# brose_24v_logic.net
KiCad netlist of a schematic drawn in EAGLE
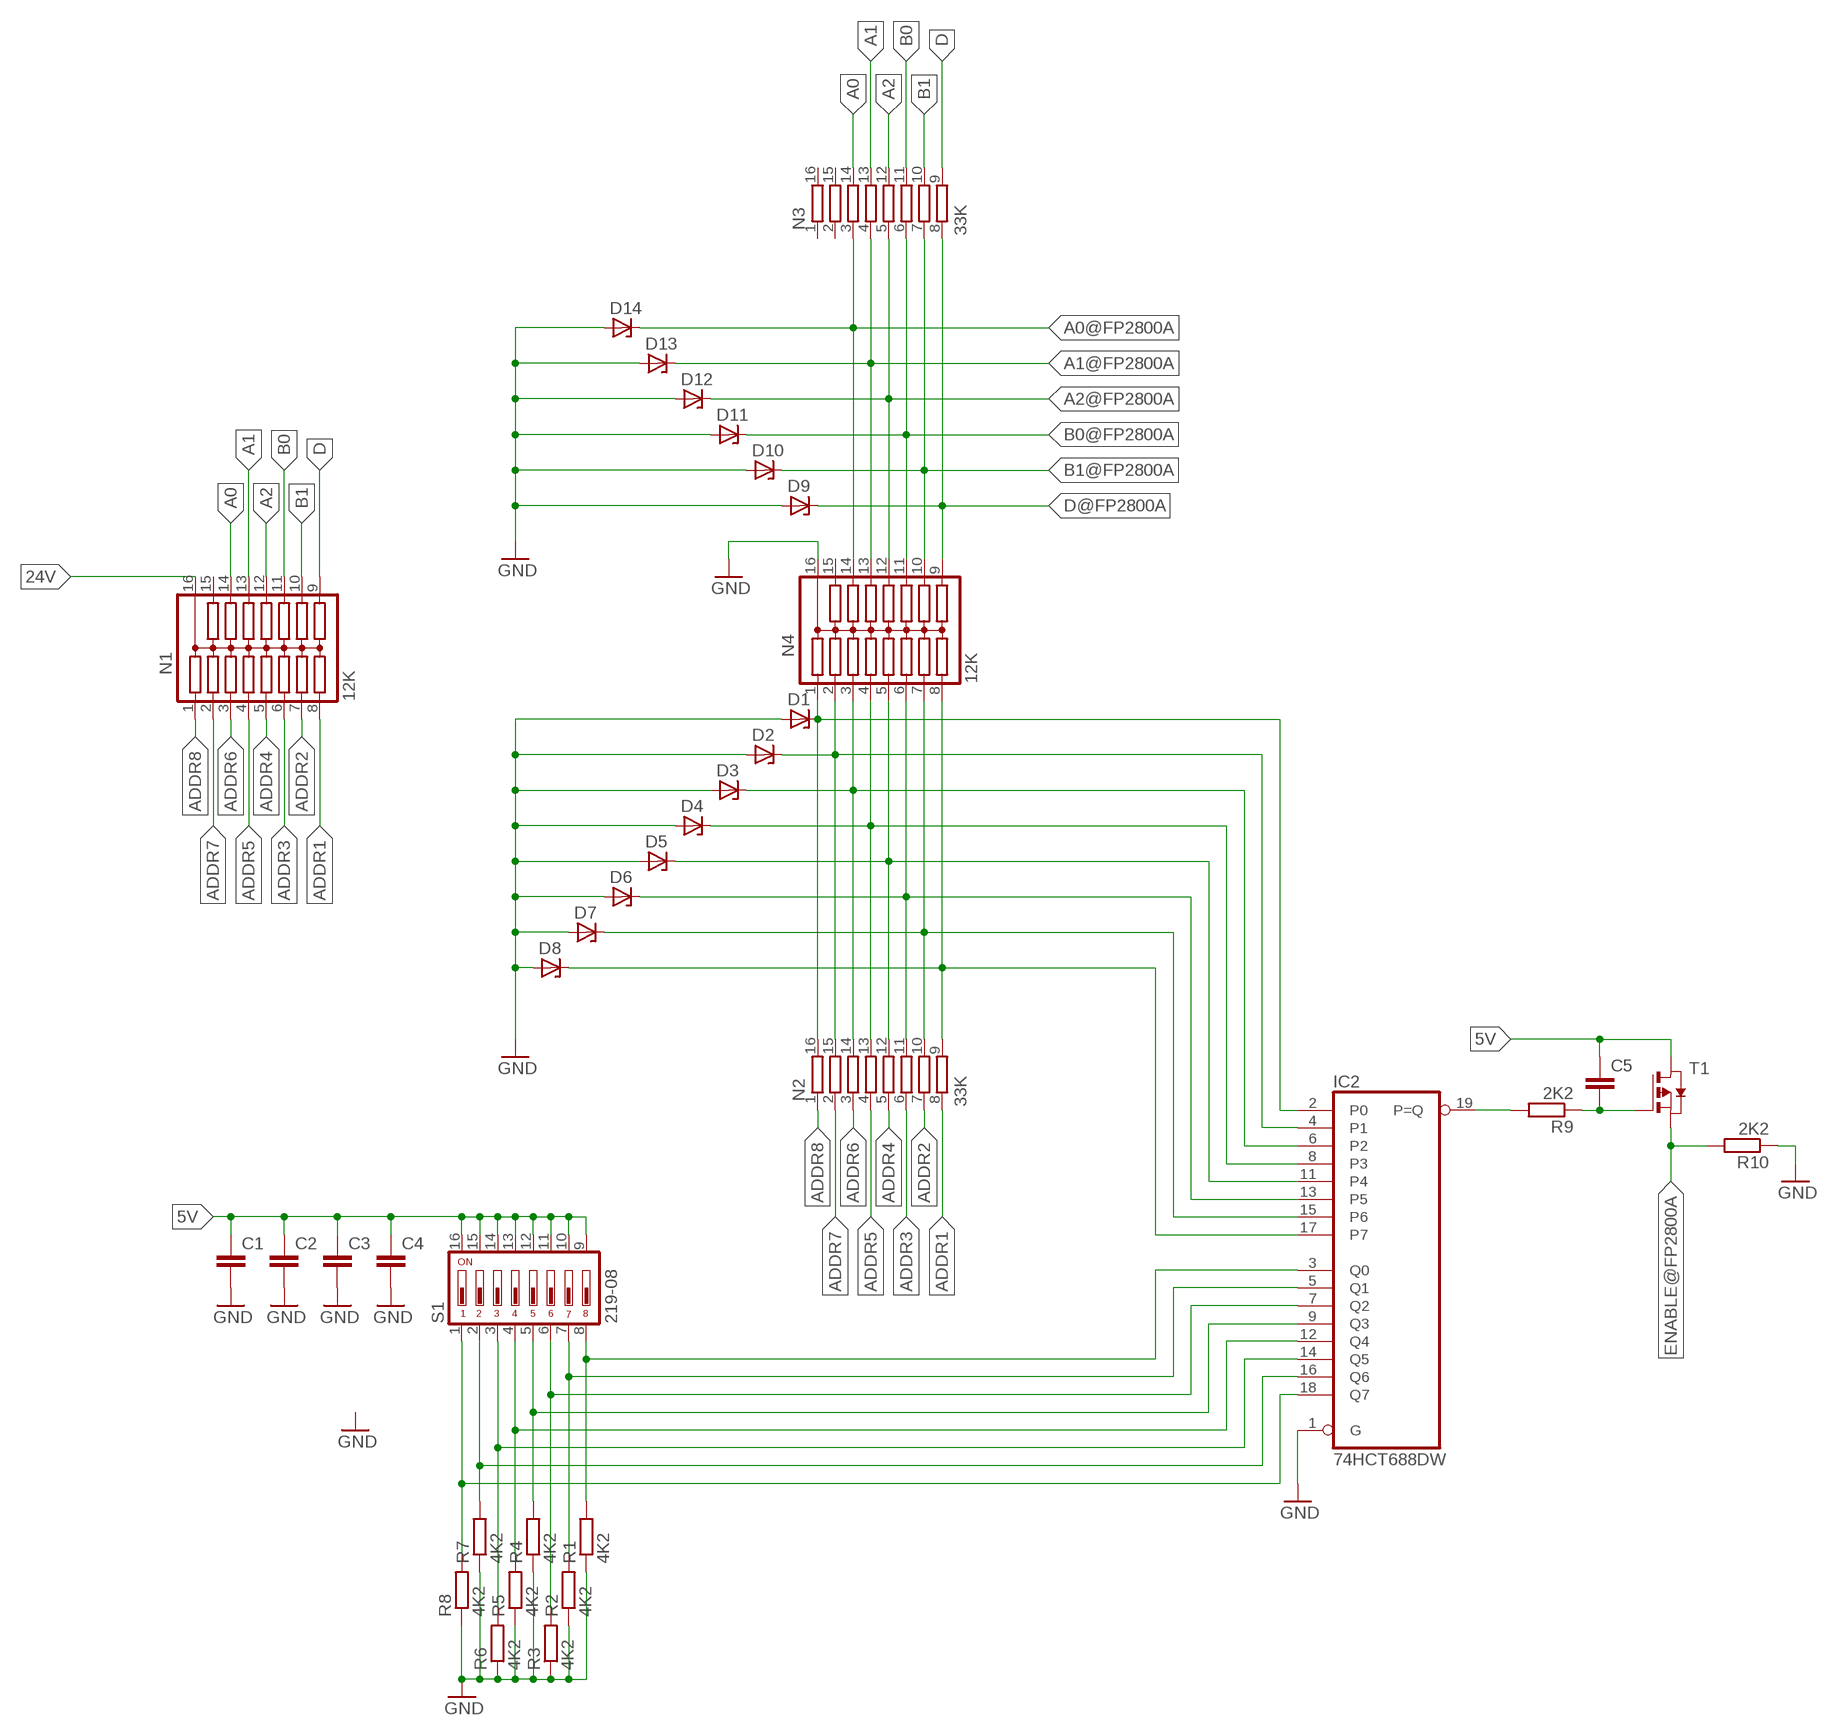
[diagram p0: schematic, sheet 1]

(export (version "E")
  (design (tool "Eeschema 10.0.6"))
  (components
    (comp (ref "C1")
      (value "C-EUC1206")
      (footprint "eagle-import:C1206")
      (libsource (lib "eagle-import") (part "C-EUC1206"))
    )
    (comp (ref "C2")
      (value "C-EUC1206")
      (footprint "eagle-import:C1206")
      (libsource (lib "eagle-import") (part "C-EUC1206"))
    )
    (comp (ref "C3")
      (value "C-EUC1206")
      (footprint "eagle-import:C1206")
      (libsource (lib "eagle-import") (part "C-EUC1206"))
    )
    (comp (ref "C4")
      (value "C-EUC1206")
      (footprint "eagle-import:C1206")
      (libsource (lib "eagle-import") (part "C-EUC1206"))
    )
    (comp (ref "C5")
      (value "C-EUC1206")
      (footprint "eagle-import:C1206")
      (libsource (lib "eagle-import") (part "C-EUC1206"))
    )
    (comp (ref "D1")
      (value "ZENER-DIODESMB")
      (footprint "eagle-import:SMB")
      (libsource (lib "eagle-import") (part "ZENER-DIODESMB"))
    )
    (comp (ref "D2")
      (value "ZENER-DIODESMB")
      (footprint "eagle-import:SMB")
      (libsource (lib "eagle-import") (part "ZENER-DIODESMB"))
    )
    (comp (ref "D3")
      (value "ZENER-DIODESMB")
      (footprint "eagle-import:SMB")
      (libsource (lib "eagle-import") (part "ZENER-DIODESMB"))
    )
    (comp (ref "D4")
      (value "ZENER-DIODESMB")
      (footprint "eagle-import:SMB")
      (libsource (lib "eagle-import") (part "ZENER-DIODESMB"))
    )
    (comp (ref "D5")
      (value "ZENER-DIODESMB")
      (footprint "eagle-import:SMB")
      (libsource (lib "eagle-import") (part "ZENER-DIODESMB"))
    )
    (comp (ref "D6")
      (value "ZENER-DIODESMB")
      (footprint "eagle-import:SMB")
      (libsource (lib "eagle-import") (part "ZENER-DIODESMB"))
    )
    (comp (ref "D7")
      (value "ZENER-DIODESMB")
      (footprint "eagle-import:SMB")
      (libsource (lib "eagle-import") (part "ZENER-DIODESMB"))
    )
    (comp (ref "D8")
      (value "ZENER-DIODESMB")
      (footprint "eagle-import:SMB")
      (libsource (lib "eagle-import") (part "ZENER-DIODESMB"))
    )
    (comp (ref "D9")
      (value "ZENER-DIODESMB")
      (footprint "eagle-import:SMB")
      (libsource (lib "eagle-import") (part "ZENER-DIODESMB"))
    )
    (comp (ref "D10")
      (value "ZENER-DIODESMB")
      (footprint "eagle-import:SMB")
      (libsource (lib "eagle-import") (part "ZENER-DIODESMB"))
    )
    (comp (ref "D11")
      (value "ZENER-DIODESMB")
      (footprint "eagle-import:SMB")
      (libsource (lib "eagle-import") (part "ZENER-DIODESMB"))
    )
    (comp (ref "D12")
      (value "ZENER-DIODESMB")
      (footprint "eagle-import:SMB")
      (libsource (lib "eagle-import") (part "ZENER-DIODESMB"))
    )
    (comp (ref "D13")
      (value "ZENER-DIODESMB")
      (footprint "eagle-import:SMB")
      (libsource (lib "eagle-import") (part "ZENER-DIODESMB"))
    )
    (comp (ref "D14")
      (value "ZENER-DIODESMB")
      (footprint "eagle-import:SMB")
      (libsource (lib "eagle-import") (part "ZENER-DIODESMB"))
    )
    (comp (ref "IC2")
      (value "74HCT688DW")
      (footprint "eagle-import:SO20W")
      (libsource (lib "eagle-import") (part "74688DWHCT"))
    )
    (comp (ref "N1")
      (value "12K")
      (footprint "eagle-import:SOMC16")
      (fields (field (name "MPN") "SOMC160115R0GDC"))
      (libsource (lib "eagle-import") (part "15RSOMC"))
    )
    (comp (ref "N2")
      (value "33K")
      (footprint "eagle-import:4816P")
      (fields (field (name "MF") "BOURNS, INC.") (field (name "MPN") "4816P-T01-684LF"))
      (libsource (lib "eagle-import") (part "4816P-T01"))
    )
    (comp (ref "N3")
      (value "33K")
      (footprint "eagle-import:4816P")
      (fields (field (name "MF") "BOURNS, INC.") (field (name "MPN") "4816P-T01-684LF"))
      (libsource (lib "eagle-import") (part "4816P-T01"))
    )
    (comp (ref "N4")
      (value "12K")
      (footprint "eagle-import:SOMC16")
      (fields (field (name "MPN") "SOMC160115R0GDC"))
      (libsource (lib "eagle-import") (part "15RSOMC"))
    )
    (comp (ref "R1")
      (value "4K2")
      (footprint "eagle-import:R1206")
      (libsource (lib "eagle-import") (part "R-EU_R1206"))
    )
    (comp (ref "R2")
      (value "4K2")
      (footprint "eagle-import:R1206")
      (libsource (lib "eagle-import") (part "R-EU_R1206"))
    )
    (comp (ref "R3")
      (value "4K2")
      (footprint "eagle-import:R1206")
      (libsource (lib "eagle-import") (part "R-EU_R1206"))
    )
    (comp (ref "R4")
      (value "4K2")
      (footprint "eagle-import:R1206")
      (libsource (lib "eagle-import") (part "R-EU_R1206"))
    )
    (comp (ref "R5")
      (value "4K2")
      (footprint "eagle-import:R1206")
      (libsource (lib "eagle-import") (part "R-EU_R1206"))
    )
    (comp (ref "R6")
      (value "4K2")
      (footprint "eagle-import:R1206")
      (libsource (lib "eagle-import") (part "R-EU_R1206"))
    )
    (comp (ref "R7")
      (value "4K2")
      (footprint "eagle-import:R1206")
      (libsource (lib "eagle-import") (part "R-EU_R1206"))
    )
    (comp (ref "R8")
      (value "4K2")
      (footprint "eagle-import:R1206")
      (libsource (lib "eagle-import") (part "R-EU_R1206"))
    )
    (comp (ref "R9")
      (value "2K2")
      (footprint "eagle-import:R1206")
      (libsource (lib "eagle-import") (part "R-EU_R1206"))
    )
    (comp (ref "R10")
      (value "2K2")
      (footprint "eagle-import:R1206")
      (libsource (lib "eagle-import") (part "R-EU_R1206"))
    )
    (comp (ref "S1")
      (value "219-08")
      (footprint "eagle-import:CTS-219-08")
      (libsource (lib "eagle-import") (part "219-08"))
    )
    (comp (ref "T1")
      (value "PMOSSOT23")
      (footprint "eagle-import:SOT-23")
      (libsource (lib "eagle-import") (part "PMOSSOT23"))
    )
  )
  (nets
    (net (code "1") (name "5V") (class "Default")
      (node (ref "C1") (pin "1") (pinfunction "1_1") (pintype "passive"))
      (node (ref "C2") (pin "1") (pinfunction "1_1") (pintype "passive"))
      (node (ref "C3") (pin "1") (pinfunction "1_1") (pintype "passive"))
      (node (ref "C4") (pin "1") (pinfunction "1_1") (pintype "passive"))
      (node (ref "C5") (pin "1") (pinfunction "1_1") (pintype "passive"))
      (node (ref "S1") (pin "10") (pinfunction "10_10") (pintype "passive"))
      (node (ref "S1") (pin "11") (pinfunction "11_11") (pintype "passive"))
      (node (ref "S1") (pin "12") (pinfunction "12_12") (pintype "passive"))
      (node (ref "S1") (pin "13") (pinfunction "13_13") (pintype "passive"))
      (node (ref "S1") (pin "14") (pinfunction "14_14") (pintype "passive"))
      (node (ref "S1") (pin "15") (pinfunction "15_15") (pintype "passive"))
      (node (ref "S1") (pin "16") (pinfunction "16_16") (pintype "passive"))
      (node (ref "S1") (pin "9") (pinfunction "9_9") (pintype "passive"))
      (node (ref "T1") (pin "1") (pinfunction "D_1") (pintype "passive"))
    )
    (net (code "2") (name "24V") (class "Default")
      (node (ref "N1") (pin "16") (pinfunction "16_16") (pintype "passive"))
    )
    (net (code "3") (name "A0") (class "Default")
      (node (ref "N1") (pin "14") (pinfunction "14_14") (pintype "passive"))
      (node (ref "N3") (pin "14") (pinfunction "14_14") (pintype "passive"))
    )
    (net (code "4") (name "A0@FP2800A") (class "Default")
      (node (ref "D14") (pin "C") (pinfunction "C_C") (pintype "passive"))
      (node (ref "N3") (pin "3") (pinfunction "3_3") (pintype "passive"))
      (node (ref "N4") (pin "14") (pinfunction "14_14") (pintype "passive"))
    )
    (net (code "5") (name "A1") (class "Default")
      (node (ref "N1") (pin "13") (pinfunction "13_13") (pintype "passive"))
      (node (ref "N3") (pin "13") (pinfunction "13_13") (pintype "passive"))
    )
    (net (code "6") (name "A1@FP2800A") (class "Default")
      (node (ref "D13") (pin "C") (pinfunction "C_C") (pintype "passive"))
      (node (ref "N3") (pin "4") (pinfunction "4_4") (pintype "passive"))
      (node (ref "N4") (pin "13") (pinfunction "13_13") (pintype "passive"))
    )
    (net (code "7") (name "A2") (class "Default")
      (node (ref "N1") (pin "12") (pinfunction "12_12") (pintype "passive"))
      (node (ref "N3") (pin "12") (pinfunction "12_12") (pintype "passive"))
    )
    (net (code "8") (name "A2@FP2800A") (class "Default")
      (node (ref "D12") (pin "C") (pinfunction "C_C") (pintype "passive"))
      (node (ref "N3") (pin "5") (pinfunction "5_5") (pintype "passive"))
      (node (ref "N4") (pin "12") (pinfunction "12_12") (pintype "passive"))
    )
    (net (code "9") (name "ADDR1") (class "Default")
      (node (ref "N1") (pin "8") (pinfunction "8_8") (pintype "passive"))
      (node (ref "N2") (pin "8") (pinfunction "8_8") (pintype "passive"))
    )
    (net (code "10") (name "ADDR2") (class "Default")
      (node (ref "N1") (pin "7") (pinfunction "7_7") (pintype "passive"))
      (node (ref "N2") (pin "7") (pinfunction "7_7") (pintype "passive"))
    )
    (net (code "11") (name "ADDR3") (class "Default")
      (node (ref "N1") (pin "6") (pinfunction "6_6") (pintype "passive"))
      (node (ref "N2") (pin "6") (pinfunction "6_6") (pintype "passive"))
    )
    (net (code "12") (name "ADDR4") (class "Default")
      (node (ref "N1") (pin "5") (pinfunction "5_5") (pintype "passive"))
      (node (ref "N2") (pin "5") (pinfunction "5_5") (pintype "passive"))
    )
    (net (code "13") (name "ADDR5") (class "Default")
      (node (ref "N1") (pin "4") (pinfunction "4_4") (pintype "passive"))
      (node (ref "N2") (pin "4") (pinfunction "4_4") (pintype "passive"))
    )
    (net (code "14") (name "ADDR6") (class "Default")
      (node (ref "N1") (pin "3") (pinfunction "3_3") (pintype "passive"))
      (node (ref "N2") (pin "3") (pinfunction "3_3") (pintype "passive"))
    )
    (net (code "15") (name "ADDR7") (class "Default")
      (node (ref "N1") (pin "2") (pinfunction "2_2") (pintype "passive"))
      (node (ref "N2") (pin "2") (pinfunction "2_2") (pintype "passive"))
    )
    (net (code "16") (name "ADDR8") (class "Default")
      (node (ref "N1") (pin "1") (pinfunction "1_1") (pintype "passive"))
      (node (ref "N2") (pin "1") (pinfunction "1_1") (pintype "passive"))
    )
    (net (code "17") (name "B0") (class "Default")
      (node (ref "N1") (pin "11") (pinfunction "11_11") (pintype "passive"))
      (node (ref "N3") (pin "11") (pinfunction "11_11") (pintype "passive"))
    )
    (net (code "18") (name "B0@FP2800A") (class "Default")
      (node (ref "D11") (pin "C") (pinfunction "C_C") (pintype "passive"))
      (node (ref "N3") (pin "6") (pinfunction "6_6") (pintype "passive"))
      (node (ref "N4") (pin "11") (pinfunction "11_11") (pintype "passive"))
    )
    (net (code "19") (name "B1") (class "Default")
      (node (ref "N1") (pin "10") (pinfunction "10_10") (pintype "passive"))
      (node (ref "N3") (pin "10") (pinfunction "10_10") (pintype "passive"))
    )
    (net (code "20") (name "B1@FP2800A") (class "Default")
      (node (ref "D10") (pin "C") (pinfunction "C_C") (pintype "passive"))
      (node (ref "N3") (pin "7") (pinfunction "7_7") (pintype "passive"))
      (node (ref "N4") (pin "10") (pinfunction "10_10") (pintype "passive"))
    )
    (net (code "21") (name "D") (class "Default")
      (node (ref "N1") (pin "9") (pinfunction "9_9") (pintype "passive"))
      (node (ref "N3") (pin "9") (pinfunction "9_9") (pintype "passive"))
    )
    (net (code "22") (name "D@FP2800A") (class "Default")
      (node (ref "D9") (pin "C") (pinfunction "C_C") (pintype "passive"))
      (node (ref "N3") (pin "8") (pinfunction "8_8") (pintype "passive"))
      (node (ref "N4") (pin "9") (pinfunction "9_9") (pintype "passive"))
    )
    (net (code "23") (name "ENABLE@FP2800A") (class "Default")
      (node (ref "R10") (pin "2") (pinfunction "2_2") (pintype "passive"))
      (node (ref "T1") (pin "2") (pinfunction "S_2") (pintype "passive"))
    )
    (net (code "24") (name "GND") (class "Default")
      (node (ref "C1") (pin "2") (pinfunction "2_2") (pintype "passive"))
      (node (ref "C2") (pin "2") (pinfunction "2_2") (pintype "passive"))
      (node (ref "C3") (pin "2") (pinfunction "2_2") (pintype "passive"))
      (node (ref "C4") (pin "2") (pinfunction "2_2") (pintype "passive"))
      (node (ref "D1") (pin "A") (pinfunction "A_A") (pintype "passive"))
      (node (ref "D10") (pin "A") (pinfunction "A_A") (pintype "passive"))
      (node (ref "D11") (pin "A") (pinfunction "A_A") (pintype "passive"))
      (node (ref "D12") (pin "A") (pinfunction "A_A") (pintype "passive"))
      (node (ref "D13") (pin "A") (pinfunction "A_A") (pintype "passive"))
      (node (ref "D14") (pin "A") (pinfunction "A_A") (pintype "passive"))
      (node (ref "D2") (pin "A") (pinfunction "A_A") (pintype "passive"))
      (node (ref "D3") (pin "A") (pinfunction "A_A") (pintype "passive"))
      (node (ref "D4") (pin "A") (pinfunction "A_A") (pintype "passive"))
      (node (ref "D5") (pin "A") (pinfunction "A_A") (pintype "passive"))
      (node (ref "D6") (pin "A") (pinfunction "A_A") (pintype "passive"))
      (node (ref "D7") (pin "A") (pinfunction "A_A") (pintype "passive"))
      (node (ref "D8") (pin "A") (pinfunction "A_A") (pintype "passive"))
      (node (ref "D9") (pin "A") (pinfunction "A_A") (pintype "passive"))
      (node (ref "IC2") (pin "1") (pinfunction "G_1") (pintype "input"))
      (node (ref "N4") (pin "16") (pinfunction "16_16") (pintype "passive"))
      (node (ref "R1") (pin "1") (pinfunction "1_1") (pintype "passive"))
      (node (ref "R10") (pin "1") (pinfunction "1_1") (pintype "passive"))
      (node (ref "R2") (pin "1") (pinfunction "1_1") (pintype "passive"))
      (node (ref "R3") (pin "1") (pinfunction "1_1") (pintype "passive"))
      (node (ref "R4") (pin "1") (pinfunction "1_1") (pintype "passive"))
      (node (ref "R5") (pin "1") (pinfunction "1_1") (pintype "passive"))
      (node (ref "R6") (pin "1") (pinfunction "1_1") (pintype "passive"))
      (node (ref "R7") (pin "1") (pinfunction "1_1") (pintype "passive"))
      (node (ref "R8") (pin "1") (pinfunction "1_1") (pintype "passive"))
    )
    (net (code "25") (name "Net-(IC2A-P0)") (class "Default")
      (node (ref "D1") (pin "C") (pinfunction "C_C") (pintype "passive"))
      (node (ref "IC2") (pin "2") (pinfunction "P0_2") (pintype "input"))
      (node (ref "N2") (pin "16") (pinfunction "16_16") (pintype "passive"))
      (node (ref "N4") (pin "1") (pinfunction "1_1") (pintype "passive"))
    )
    (net (code "26") (name "Net-(IC2A-P1)") (class "Default")
      (node (ref "D2") (pin "C") (pinfunction "C_C") (pintype "passive"))
      (node (ref "IC2") (pin "4") (pinfunction "P1_4") (pintype "input"))
      (node (ref "N2") (pin "15") (pinfunction "15_15") (pintype "passive"))
      (node (ref "N4") (pin "2") (pinfunction "2_2") (pintype "passive"))
    )
    (net (code "27") (name "Net-(IC2A-P2)") (class "Default")
      (node (ref "D3") (pin "C") (pinfunction "C_C") (pintype "passive"))
      (node (ref "IC2") (pin "6") (pinfunction "P2_6") (pintype "input"))
      (node (ref "N2") (pin "14") (pinfunction "14_14") (pintype "passive"))
      (node (ref "N4") (pin "3") (pinfunction "3_3") (pintype "passive"))
    )
    (net (code "28") (name "Net-(IC2A-P3)") (class "Default")
      (node (ref "D4") (pin "C") (pinfunction "C_C") (pintype "passive"))
      (node (ref "IC2") (pin "8") (pinfunction "P3_8") (pintype "input"))
      (node (ref "N2") (pin "13") (pinfunction "13_13") (pintype "passive"))
      (node (ref "N4") (pin "4") (pinfunction "4_4") (pintype "passive"))
    )
    (net (code "29") (name "Net-(IC2A-P4)") (class "Default")
      (node (ref "D5") (pin "C") (pinfunction "C_C") (pintype "passive"))
      (node (ref "IC2") (pin "11") (pinfunction "P4_11") (pintype "input"))
      (node (ref "N2") (pin "12") (pinfunction "12_12") (pintype "passive"))
      (node (ref "N4") (pin "5") (pinfunction "5_5") (pintype "passive"))
    )
    (net (code "30") (name "Net-(IC2A-P5)") (class "Default")
      (node (ref "D6") (pin "C") (pinfunction "C_C") (pintype "passive"))
      (node (ref "IC2") (pin "13") (pinfunction "P5_13") (pintype "input"))
      (node (ref "N2") (pin "11") (pinfunction "11_11") (pintype "passive"))
      (node (ref "N4") (pin "6") (pinfunction "6_6") (pintype "passive"))
    )
    (net (code "31") (name "Net-(IC2A-P6)") (class "Default")
      (node (ref "D7") (pin "C") (pinfunction "C_C") (pintype "passive"))
      (node (ref "IC2") (pin "15") (pinfunction "P6_15") (pintype "input"))
      (node (ref "N2") (pin "10") (pinfunction "10_10") (pintype "passive"))
      (node (ref "N4") (pin "7") (pinfunction "7_7") (pintype "passive"))
    )
    (net (code "32") (name "Net-(IC2A-P7)") (class "Default")
      (node (ref "D8") (pin "C") (pinfunction "C_C") (pintype "passive"))
      (node (ref "IC2") (pin "17") (pinfunction "P7_17") (pintype "input"))
      (node (ref "N2") (pin "9") (pinfunction "9_9") (pintype "passive"))
      (node (ref "N4") (pin "8") (pinfunction "8_8") (pintype "passive"))
    )
    (net (code "33") (name "Net-(IC2A-P=Q)") (class "Default")
      (node (ref "IC2") (pin "19") (pinfunction "P=Q_19") (pintype "output"))
      (node (ref "R9") (pin "2") (pinfunction "2_2") (pintype "passive"))
    )
    (net (code "34") (name "Net-(IC2A-Q0)") (class "Default")
      (node (ref "IC2") (pin "3") (pinfunction "Q0_3") (pintype "input"))
      (node (ref "R1") (pin "2") (pinfunction "2_2") (pintype "passive"))
      (node (ref "S1") (pin "8") (pinfunction "8_8") (pintype "passive"))
    )
    (net (code "35") (name "Net-(IC2A-Q1)") (class "Default")
      (node (ref "IC2") (pin "5") (pinfunction "Q1_5") (pintype "input"))
      (node (ref "R2") (pin "2") (pinfunction "2_2") (pintype "passive"))
      (node (ref "S1") (pin "7") (pinfunction "7_7") (pintype "passive"))
    )
    (net (code "36") (name "Net-(IC2A-Q2)") (class "Default")
      (node (ref "IC2") (pin "7") (pinfunction "Q2_7") (pintype "input"))
      (node (ref "R3") (pin "2") (pinfunction "2_2") (pintype "passive"))
      (node (ref "S1") (pin "6") (pinfunction "6_6") (pintype "passive"))
    )
    (net (code "37") (name "Net-(IC2A-Q3)") (class "Default")
      (node (ref "IC2") (pin "9") (pinfunction "Q3_9") (pintype "input"))
      (node (ref "R4") (pin "2") (pinfunction "2_2") (pintype "passive"))
      (node (ref "S1") (pin "5") (pinfunction "5_5") (pintype "passive"))
    )
    (net (code "38") (name "Net-(IC2A-Q4)") (class "Default")
      (node (ref "IC2") (pin "12") (pinfunction "Q4_12") (pintype "input"))
      (node (ref "R5") (pin "2") (pinfunction "2_2") (pintype "passive"))
      (node (ref "S1") (pin "4") (pinfunction "4_4") (pintype "passive"))
    )
    (net (code "39") (name "Net-(IC2A-Q5)") (class "Default")
      (node (ref "IC2") (pin "14") (pinfunction "Q5_14") (pintype "input"))
      (node (ref "R6") (pin "2") (pinfunction "2_2") (pintype "passive"))
      (node (ref "S1") (pin "3") (pinfunction "3_3") (pintype "passive"))
    )
    (net (code "40") (name "Net-(IC2A-Q6)") (class "Default")
      (node (ref "IC2") (pin "16") (pinfunction "Q6_16") (pintype "input"))
      (node (ref "R7") (pin "2") (pinfunction "2_2") (pintype "passive"))
      (node (ref "S1") (pin "2") (pinfunction "2_2") (pintype "passive"))
    )
    (net (code "41") (name "Net-(IC2A-Q7)") (class "Default")
      (node (ref "IC2") (pin "18") (pinfunction "Q7_18") (pintype "input"))
      (node (ref "R8") (pin "2") (pinfunction "2_2") (pintype "passive"))
      (node (ref "S1") (pin "1") (pinfunction "1_1") (pintype "passive"))
    )
    (net (code "42") (name "Net-(T1-G)") (class "Default")
      (node (ref "C5") (pin "2") (pinfunction "2_2") (pintype "passive"))
      (node (ref "R9") (pin "1") (pinfunction "1_1") (pintype "passive"))
      (node (ref "T1") (pin "3") (pinfunction "G_3") (pintype "passive"))
    )
    (net (code "43") (name "unconnected-(N1-Pad15)") (class "Default")
      (node (ref "N1") (pin "15") (pinfunction "15_15") (pintype "passive"))
    )
    (net (code "44") (name "unconnected-(N3-Pad1)") (class "Default")
      (node (ref "N3") (pin "1") (pinfunction "1_1") (pintype "passive"))
    )
    (net (code "45") (name "unconnected-(N3-Pad2)") (class "Default")
      (node (ref "N3") (pin "2") (pinfunction "2_2") (pintype "passive"))
    )
    (net (code "46") (name "unconnected-(N3-Pad15)") (class "Default")
      (node (ref "N3") (pin "15") (pinfunction "15_15") (pintype "passive"))
    )
    (net (code "47") (name "unconnected-(N3-Pad16)") (class "Default")
      (node (ref "N3") (pin "16") (pinfunction "16_16") (pintype "passive"))
    )
    (net (code "48") (name "unconnected-(N4-Pad15)") (class "Default")
      (node (ref "N4") (pin "15") (pinfunction "15_15") (pintype "passive"))
    )
  )
)
